# OK.net
KiCad netlist of a schematic drawn in Altium Designer
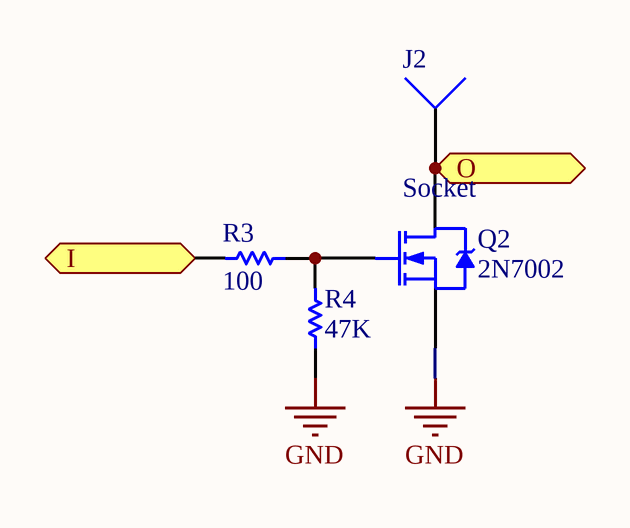
[diagram p0: OK.SchDoc]

(export (version "E")
  (design (tool "Eeschema 10.0.6"))
  (components
    (comp (ref "J2")
      (value "Socket")
      (footprint "PIN#001")
      (fields (field (name "PUBLISHER") "Altium Limited"))
      (libsource (lib "Miscellaneous Connectors") (part "Socket"))
    )
    (comp (ref "Q2")
      (value "2N7002")
      (footprint "SOT-23_N")
      (description "HEXFET Power MOSFET")
      (fields (field (name "PUBLISHER") "Altium Limited"))
      (libsource (lib "IR Discrete MOSFET - Power") (part "IRLML2402"))
    )
    (comp (ref "R3")
      (value "100")
      (footprint "0603x")
      (description "Resistor")
      (fields (field (name "PUBLISHER") "Altium Limited"))
      (libsource (lib "Miscellaneous Devices") (part "Res1"))
    )
    (comp (ref "R4")
      (value "47K")
      (footprint "0603x")
      (description "Resistor")
      (fields (field (name "PUBLISHER") "Altium Limited"))
      (libsource (lib "Miscellaneous Devices") (part "Res1"))
    )
  )
  (nets
    (net (code "1") (name "/I") (class "Default")
      (node (ref "R3") (pin "2") (pinfunction "2_2") (pintype "passive"))
    )
    (net (code "2") (name "/O") (class "Default")
      (node (ref "J2") (pin "1") (pinfunction "1_1") (pintype "passive"))
      (node (ref "Q2") (pin "3") (pinfunction "D_3") (pintype "passive"))
    )
    (net (code "3") (name "GND") (class "Default")
      (node (ref "Q2") (pin "2") (pinfunction "S_2") (pintype "passive"))
      (node (ref "R4") (pin "1") (pinfunction "1_1") (pintype "passive"))
    )
    (net (code "4") (name "Net-(Q2-G)") (class "Default")
      (node (ref "Q2") (pin "1") (pinfunction "G_1") (pintype "passive"))
      (node (ref "R3") (pin "1") (pinfunction "1_1") (pintype "passive"))
      (node (ref "R4") (pin "2") (pinfunction "2_2") (pintype "passive"))
    )
  )
)
